# SCHEMATIC_ESP32C3FN4_8thJune2023.net
KiCad netlist of a schematic drawn in Altium Designer
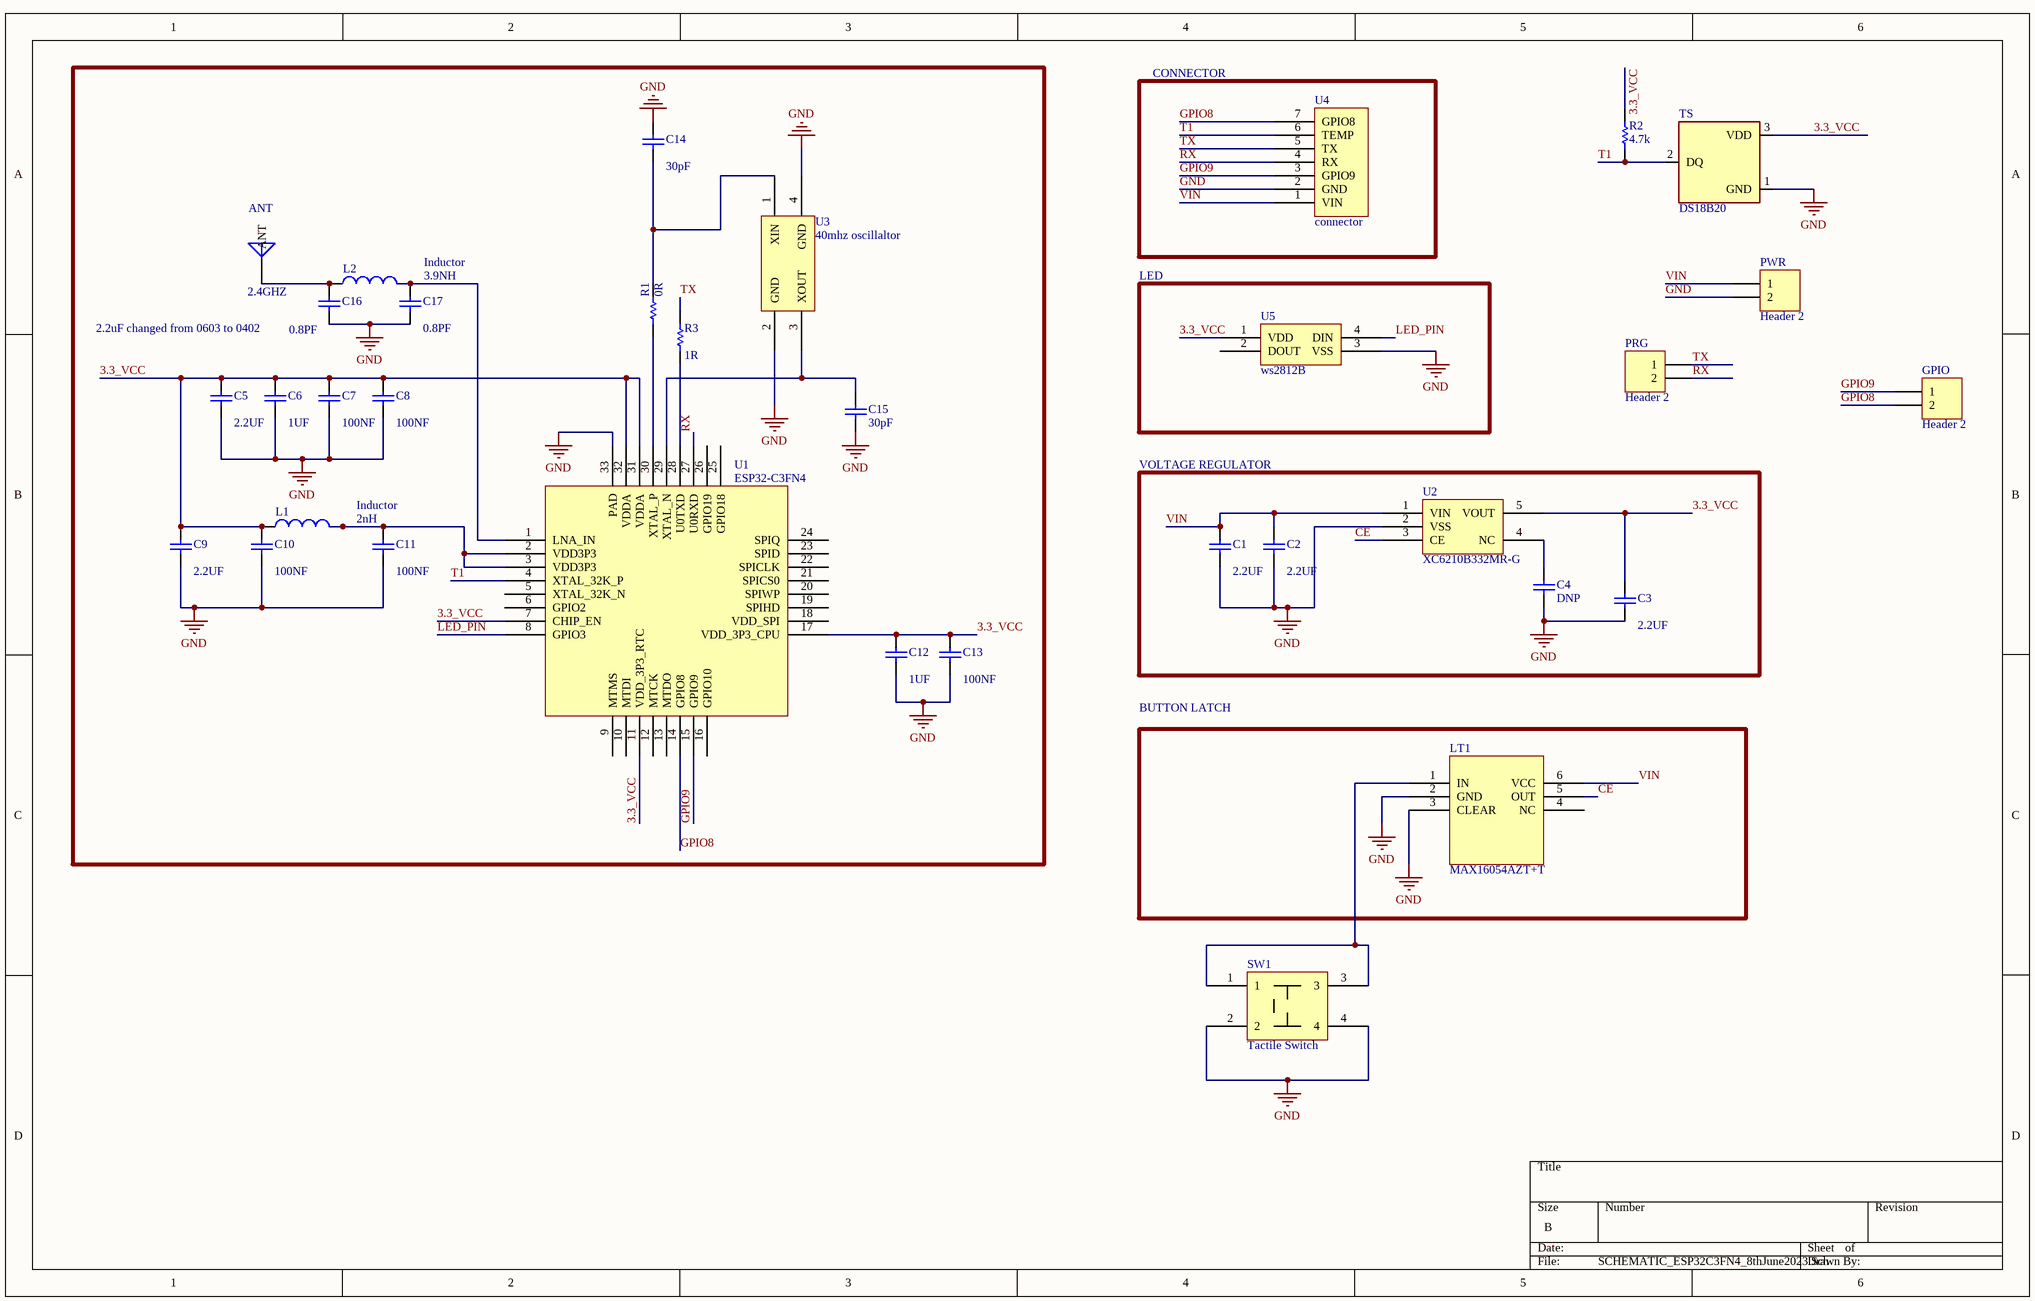
[diagram p0: SCHEMATIC_ESP32C3FN4_8thJune2023.SchDoc]

(export (version "E")
  (design (tool "Eeschema 10.0.6"))
  (components
    (comp (ref "ANT")
      (value "2.4GHZ")
      (footprint "XDCR_2450AT18B100E")
      (description "Generic Antennals")
      (fields (field (name "PUBLISHER") "Altium Limited"))
      (libsource (lib "Miscellaneous Devices") (part "Antenna"))
    )
    (comp (ref "C1")
      (value "2.2UF")
      (footprint "0402-A")
      (description "16V 2.2uF X6S ±10% 0402 Multilayer Ceramic Capacitors MLCC - SMD/SMT ROHS")
      (fields (field (name "Comment") "GRM188C71C225KE11D") (field (name "PUBLISHER") "Altium Limited"))
      (libsource (lib "Miscellaneous Devices") (part "Cap"))
    )
    (comp (ref "C2")
      (value "2.2UF")
      (footprint "0402-A")
      (description "16V 2.2uF X6S ±10% 0402 Multilayer Ceramic Capacitors MLCC - SMD/SMT ROHS")
      (fields (field (name "Comment") "GRM188C71C225KE11D") (field (name "PUBLISHER") "Altium Limited"))
      (libsource (lib "Miscellaneous Devices") (part "Cap"))
    )
    (comp (ref "C3")
      (value "2.2UF")
      (footprint "0402-A")
      (description "16V 2.2uF X6S ±10% 0402 Multilayer Ceramic Capacitors MLCC - SMD/SMT ROHS")
      (fields (field (name "Comment") "GRM188C71C225KE11D") (field (name "PUBLISHER") "Altium Limited"))
      (libsource (lib "Miscellaneous Devices") (part "Cap"))
    )
    (comp (ref "C4")
      (value "DNP")
      (footprint "0402")
      (description "Capacitor")
      (fields (field (name "PUBLISHER") "Altium Limited"))
      (libsource (lib "Miscellaneous Devices") (part "Cap"))
    )
    (comp (ref "C5")
      (value "2.2UF")
      (footprint "0402-A")
      (description "16V 2.2uF X6S ±10% 0402 Multilayer Ceramic Capacitors MLCC - SMD/SMT ROHS")
      (fields (field (name "Comment") "GRM188C71C225KE11D") (field (name "PUBLISHER") "Altium Limited"))
      (libsource (lib "Miscellaneous Devices") (part "Cap"))
    )
    (comp (ref "C6")
      (value "1UF")
      (footprint "0402-A")
      (description "35V 1uF ±10% 0402 Multilayer Ceramic Capacitors MLCC - SMD/SMT ROHS")
      (fields (field (name "Comment") "Cap") (field (name "PUBLISHER") "Altium Limited"))
      (libsource (lib "Miscellaneous Devices") (part "Cap"))
    )
    (comp (ref "C7")
      (value "100NF")
      (footprint "0402-A")
      (description "50V 100nF X7R ±10% 0402 Multilayer Ceramic Capacitors MLCC - SMD/SMT ROHS")
      (fields (field (name "Comment") "Cap") (field (name "PUBLISHER") "Altium Limited"))
      (libsource (lib "Miscellaneous Devices") (part "Cap"))
    )
    (comp (ref "C8")
      (value "100NF")
      (footprint "0402-A")
      (description "50V 100nF X7R ±10% 0402 Multilayer Ceramic Capacitors MLCC - SMD/SMT ROHS")
      (fields (field (name "Comment") "Cap") (field (name "PUBLISHER") "Altium Limited"))
      (libsource (lib "Miscellaneous Devices") (part "Cap"))
    )
    (comp (ref "C9")
      (value "2.2UF")
      (footprint "0402-A")
      (description "16V 2.2uF X6S ±10% 0402 Multilayer Ceramic Capacitors MLCC - SMD/SMT ROHS")
      (fields (field (name "Comment") "GRM188C71C225KE11D") (field (name "PUBLISHER") "Altium Limited"))
      (libsource (lib "Miscellaneous Devices") (part "Cap"))
    )
    (comp (ref "C10")
      (value "100NF")
      (footprint "0402-A")
      (description "50V 100nF X7R ±10% 0402 Multilayer Ceramic Capacitors MLCC - SMD/SMT ROHS")
      (fields (field (name "Comment") "Cap") (field (name "PUBLISHER") "Altium Limited"))
      (libsource (lib "Miscellaneous Devices") (part "Cap"))
    )
    (comp (ref "C11")
      (value "100NF")
      (footprint "0402-A")
      (description "50V 100nF X7R ±10% 0402 Multilayer Ceramic Capacitors MLCC - SMD/SMT ROHS")
      (fields (field (name "Comment") "Cap") (field (name "PUBLISHER") "Altium Limited"))
      (libsource (lib "Miscellaneous Devices") (part "Cap"))
    )
    (comp (ref "C12")
      (value "1UF")
      (footprint "0402-A")
      (description "35V 1uF ±10% 0402 Multilayer Ceramic Capacitors MLCC - SMD/SMT ROHS")
      (fields (field (name "Comment") "Cap") (field (name "PUBLISHER") "Altium Limited"))
      (libsource (lib "Miscellaneous Devices") (part "Cap"))
    )
    (comp (ref "C13")
      (value "100NF")
      (footprint "0402-A")
      (description "50V 100nF X7R ±10% 0402 Multilayer Ceramic Capacitors MLCC - SMD/SMT ROHS")
      (fields (field (name "Comment") "Cap") (field (name "PUBLISHER") "Altium Limited"))
      (libsource (lib "Miscellaneous Devices") (part "Cap"))
    )
    (comp (ref "C14")
      (value "30pF")
      (footprint "1608[0603]")
      (description "Capacitor")
      (fields (field (name "Comment") "Cap") (field (name "PUBLISHER") "Altium Limited"))
      (libsource (lib "Miscellaneous Devices") (part "Cap"))
    )
    (comp (ref "C15")
      (value "30pF")
      (footprint "1608[0603]")
      (description "Capacitor")
      (fields (field (name "Comment") "Cap") (field (name "PUBLISHER") "Altium Limited"))
      (libsource (lib "Miscellaneous Devices") (part "Cap"))
    )
    (comp (ref "C16")
      (value "0.8PF")
      (footprint "0402-A")
      (description "Capacitor")
      (fields (field (name "Comment") "Cap") (field (name "PUBLISHER") "Altium Limited"))
      (libsource (lib "Miscellaneous Devices") (part "Cap"))
    )
    (comp (ref "C17")
      (value "0.8PF")
      (footprint "0402-A")
      (description "Capacitor")
      (fields (field (name "Comment") "Cap") (field (name "PUBLISHER") "Altium Limited"))
      (libsource (lib "Miscellaneous Devices") (part "Cap"))
    )
    (comp (ref "GPIO")
      (value "Header 2")
      (footprint "C1206")
      (description "Header, 2-Pin")
      (fields (field (name "PUBLISHER") "Altium Limited"))
      (libsource (lib "Miscellaneous Connectors") (part "Header 2"))
    )
    (comp (ref "L1")
      (value "Inductor")
      (footprint "1608[0603]")
      (fields (field (name "ALTIUM_VALUE") "2nH") (field (name "PUBLISHER") "Altium Limited"))
      (libsource (lib "Miscellaneous Devices") (part "Inductor"))
    )
    (comp (ref "L2")
      (value "Inductor")
      (footprint "0402-A")
      (fields (field (name "ALTIUM_VALUE") "3.9NH") (field (name "PUBLISHER") "Altium Limited"))
      (libsource (lib "Miscellaneous Devices") (part "Inductor"))
    )
    (comp (ref "LT1")
      (value "MAX16054AZT+T")
      (footprint "SOT95P275X110-6N")
      (libsource (lib "Schlib1") (part "MAX16054AZT+T"))
    )
    (comp (ref "PRG")
      (value "Header 2")
      (footprint "C1206")
      (description "Header, 2-Pin")
      (fields (field (name "PUBLISHER") "Altium Limited"))
      (libsource (lib "") (part "Header 2_1"))
    )
    (comp (ref "PWR")
      (value "Header 2")
      (footprint "C1206")
      (description "Header, 2-Pin")
      (fields (field (name "PUBLISHER") "Altium Limited"))
      (libsource (lib "Miscellaneous Connectors") (part "Header 2"))
    )
    (comp (ref "R1")
      (value "0R")
      (footprint "0402-A")
      (description "62.5mW Thick Film Resistors ±800ppm/℃ ±1% 0Ω 0402 Chip Resistor - Surface Mount ROHS")
      (fields (field (name "Comment") "Res1") (field (name "PUBLISHER") "Altium Limited"))
      (libsource (lib "Miscellaneous Devices") (part "Res1"))
    )
    (comp (ref "R2")
      (value "4.7k")
      (footprint "1608[0603]")
      (description "±5% 4.7kΩ 0603 Chip Resistor - Surface Mount ROHS")
      (fields (field (name "Comment") "SCR0603J4K7") (field (name "PUBLISHER") "Altium Limited"))
      (libsource (lib "Miscellaneous Devices") (part "Res1"))
    )
    (comp (ref "R3")
      (value "1R")
      (footprint "0402-A")
      (description "62.5mW Thick Film Resistors ±1% ±200ppm/℃ 1Ω 0402 Chip Resistor - Surface Mount ROHS")
      (fields (field (name "Comment") "Res1") (field (name "PUBLISHER") "Altium Limited"))
      (libsource (lib "Miscellaneous Devices") (part "Res1"))
    )
    (comp (ref "SW1")
      (value "Tactile Switch")
      (footprint "SKRBACE010")
      (libsource (lib "Schlib1") (part "Tactile Switch"))
    )
    (comp (ref "TS")
      (value "DS18B20")
      (footprint "TO-92-TO92127P495H2044-3")
      (description "Temperature Sensor Digital, Local -55Â°C ~ 125Â°C 12 b TO-92-3")
      (fields (field (name "MF") "Maxim Integrated"))
      (libsource (lib "epsschmtc") (part "DS18B20"))
    )
    (comp (ref "U1")
      (value "ESP32-C3FN4")
      (footprint "QFN50P500X500X90-33N-D")
      (libsource (lib "Schlib1") (part "ESP32-C3F"))
    )
    (comp (ref "U2")
      (value "XC6210B332MR-G")
      (footprint "SOT95P280X130-5N")
      (description "700mA 60dB@(1kHz) Fixed 3.3V~3.3V Positive 6V SOT-25 Linear Voltage Regulators (LDO) ROHS")
      (libsource (lib "Schlib1") (part "XC6210B332MR-G"))
    )
    (comp (ref "U3")
      (value "40mhz oscillaltor")
      (footprint "CRYSTAL-SMD_4P-L3.2-W2.5-BL")
      (description "C3003278")
      (libsource (lib "Schlib1") (part "40mhz oscillaltor"))
    )
    (comp (ref "U4") (value "connector") (libsource (lib "Schlib1") (part "connector")))
    (comp (ref "U5")
      (value "ws2812B")
      (footprint "COM16346")
      (description "RGB SMD5050 Light Emitting Diodes (LED) ROHS")
      (libsource (lib "Schlib1") (part "ws2812B"))
    )
  )
  (nets
    (net (code "1") (name "/3.3_VCC") (class "Default")
      (node (ref "C10") (pin "2") (pinfunction "2_2") (pintype "passive"))
      (node (ref "C12") (pin "2") (pinfunction "2_2") (pintype "passive"))
      (node (ref "C13") (pin "2") (pinfunction "2_2") (pintype "passive"))
      (node (ref "C3") (pin "2") (pinfunction "2_2") (pintype "passive"))
      (node (ref "C5") (pin "2") (pinfunction "2_2") (pintype "passive"))
      (node (ref "C6") (pin "2") (pinfunction "2_2") (pintype "passive"))
      (node (ref "C7") (pin "2") (pinfunction "2_2") (pintype "passive"))
      (node (ref "C8") (pin "2") (pinfunction "2_2") (pintype "passive"))
      (node (ref "C9") (pin "2") (pinfunction "2_2") (pintype "passive"))
      (node (ref "L1") (pin "1") (pinfunction "1_1") (pintype "passive"))
      (node (ref "R2") (pin "1") (pinfunction "1_1") (pintype "passive"))
      (node (ref "TS") (pin "3") (pinfunction "VDD_3") (pintype "power_in"))
      (node (ref "U1") (pin "11") (pinfunction "VDD_3P3_RTC_11") (pintype "passive"))
      (node (ref "U1") (pin "17") (pinfunction "VDD_3P3_CPU_17") (pintype "passive"))
      (node (ref "U1") (pin "31") (pinfunction "VDDA_31") (pintype "passive"))
      (node (ref "U1") (pin "32") (pinfunction "VDDA_32") (pintype "passive"))
      (node (ref "U1") (pin "7") (pinfunction "CHIP_EN_7") (pintype "passive"))
      (node (ref "U2") (pin "5") (pinfunction "VOUT_5") (pintype "passive"))
      (node (ref "U5") (pin "1") (pinfunction "VDD_1") (pintype "passive"))
    )
    (net (code "2") (name "/CE") (class "Default")
      (node (ref "LT1") (pin "5") (pinfunction "OUT_5") (pintype "passive"))
      (node (ref "U2") (pin "3") (pinfunction "CE_3") (pintype "passive"))
    )
    (net (code "3") (name "/GPIO8") (class "Default")
      (node (ref "GPIO") (pin "2") (pinfunction "2_2") (pintype "passive"))
      (node (ref "U1") (pin "14") (pinfunction "GPIO8_14") (pintype "passive"))
      (node (ref "U4") (pin "7") (pinfunction "GPIO8_7") (pintype "passive"))
    )
    (net (code "4") (name "/GPIO9") (class "Default")
      (node (ref "GPIO") (pin "1") (pinfunction "1_1") (pintype "passive"))
      (node (ref "U1") (pin "15") (pinfunction "GPIO9_15") (pintype "passive"))
      (node (ref "U4") (pin "3") (pinfunction "GPIO9_3") (pintype "passive"))
    )
    (net (code "5") (name "/LED_PIN") (class "Default")
      (node (ref "U1") (pin "8") (pinfunction "GPIO3_8") (pintype "passive"))
      (node (ref "U5") (pin "4") (pinfunction "DIN_4") (pintype "passive"))
    )
    (net (code "6") (name "/RX") (class "Default")
      (node (ref "PRG") (pin "2") (pinfunction "2_2") (pintype "passive"))
      (node (ref "U1") (pin "27") (pinfunction "U0RXD_27") (pintype "passive"))
      (node (ref "U4") (pin "4") (pinfunction "RX_4") (pintype "passive"))
    )
    (net (code "7") (name "/T1") (class "Default")
      (node (ref "R2") (pin "2") (pinfunction "2_2") (pintype "passive"))
      (node (ref "TS") (pin "2") (pinfunction "DQ_2") (pintype "passive"))
      (node (ref "U1") (pin "4") (pinfunction "XTAL_32K_P_4") (pintype "passive"))
      (node (ref "U4") (pin "6") (pinfunction "TEMP_6") (pintype "passive"))
    )
    (net (code "8") (name "/TX") (class "Default")
      (node (ref "PRG") (pin "1") (pinfunction "1_1") (pintype "passive"))
      (node (ref "R3") (pin "1") (pinfunction "1_1") (pintype "passive"))
      (node (ref "U4") (pin "5") (pinfunction "TX_5") (pintype "passive"))
    )
    (net (code "9") (name "/VIN") (class "Default")
      (node (ref "C1") (pin "2") (pinfunction "2_2") (pintype "passive"))
      (node (ref "C2") (pin "2") (pinfunction "2_2") (pintype "passive"))
      (node (ref "LT1") (pin "6") (pinfunction "VCC_6") (pintype "passive"))
      (node (ref "PWR") (pin "1") (pinfunction "1_1") (pintype "passive"))
      (node (ref "U2") (pin "1") (pinfunction "VIN_1") (pintype "passive"))
      (node (ref "U4") (pin "1") (pinfunction "VIN_1") (pintype "passive"))
    )
    (net (code "10") (name "GND") (class "Default")
      (node (ref "C1") (pin "1") (pinfunction "1_1") (pintype "passive"))
      (node (ref "C10") (pin "1") (pinfunction "1_1") (pintype "passive"))
      (node (ref "C11") (pin "1") (pinfunction "1_1") (pintype "passive"))
      (node (ref "C12") (pin "1") (pinfunction "1_1") (pintype "passive"))
      (node (ref "C13") (pin "1") (pinfunction "1_1") (pintype "passive"))
      (node (ref "C14") (pin "2") (pinfunction "2_2") (pintype "passive"))
      (node (ref "C15") (pin "2") (pinfunction "2_2") (pintype "passive"))
      (node (ref "C16") (pin "1") (pinfunction "1_1") (pintype "passive"))
      (node (ref "C17") (pin "1") (pinfunction "1_1") (pintype "passive"))
      (node (ref "C2") (pin "1") (pinfunction "1_1") (pintype "passive"))
      (node (ref "C3") (pin "1") (pinfunction "1_1") (pintype "passive"))
      (node (ref "C4") (pin "1") (pinfunction "1_1") (pintype "passive"))
      (node (ref "C5") (pin "1") (pinfunction "1_1") (pintype "passive"))
      (node (ref "C6") (pin "1") (pinfunction "1_1") (pintype "passive"))
      (node (ref "C7") (pin "1") (pinfunction "1_1") (pintype "passive"))
      (node (ref "C8") (pin "1") (pinfunction "1_1") (pintype "passive"))
      (node (ref "C9") (pin "1") (pinfunction "1_1") (pintype "passive"))
      (node (ref "LT1") (pin "2") (pinfunction "GND_2") (pintype "passive"))
      (node (ref "LT1") (pin "3") (pinfunction "CLEAR_3") (pintype "passive"))
      (node (ref "PWR") (pin "2") (pinfunction "2_2") (pintype "passive"))
      (node (ref "SW1") (pin "2") (pinfunction "2_2") (pintype "passive"))
      (node (ref "SW1") (pin "4") (pinfunction "4_4") (pintype "passive"))
      (node (ref "TS") (pin "1") (pinfunction "GND_1") (pintype "power_in"))
      (node (ref "U1") (pin "33") (pinfunction "PAD_33") (pintype "passive"))
      (node (ref "U2") (pin "2") (pinfunction "VSS_2") (pintype "passive"))
      (node (ref "U3") (pin "2") (pinfunction "GND_2") (pintype "passive"))
      (node (ref "U3") (pin "4") (pinfunction "GND_4") (pintype "passive"))
      (node (ref "U4") (pin "2") (pinfunction "GND_2") (pintype "passive"))
      (node (ref "U5") (pin "3") (pinfunction "VSS_3") (pintype "passive"))
    )
    (net (code "11") (name "Net-(ANT-ANT)") (class "Default")
      (node (ref "ANT") (pin "1") (pinfunction "ANT_1") (pintype "passive"))
      (node (ref "C16") (pin "2") (pinfunction "2_2") (pintype "passive"))
      (node (ref "L2") (pin "1") (pinfunction "1_1") (pintype "passive"))
    )
    (net (code "12") (name "Net-(C11-Pad2)") (class "Default")
      (node (ref "C11") (pin "2") (pinfunction "2_2") (pintype "passive"))
      (node (ref "L1") (pin "2") (pinfunction "2_2") (pintype "passive"))
      (node (ref "U1") (pin "2") (pinfunction "VDD3P3_2") (pintype "passive"))
      (node (ref "U1") (pin "3") (pinfunction "VDD3P3_3") (pintype "passive"))
    )
    (net (code "13") (name "Net-(LT1-IN)") (class "Default")
      (node (ref "LT1") (pin "1") (pinfunction "IN_1") (pintype "passive"))
      (node (ref "SW1") (pin "1") (pinfunction "1_1") (pintype "passive"))
      (node (ref "SW1") (pin "3") (pinfunction "3_3") (pintype "passive"))
    )
    (net (code "14") (name "Net-(U1-LNA_IN)") (class "Default")
      (node (ref "C17") (pin "2") (pinfunction "2_2") (pintype "passive"))
      (node (ref "L2") (pin "2") (pinfunction "2_2") (pintype "passive"))
      (node (ref "U1") (pin "1") (pinfunction "LNA_IN_1") (pintype "passive"))
    )
    (net (code "15") (name "Net-(U1-U0TXD)") (class "Default")
      (node (ref "R3") (pin "2") (pinfunction "2_2") (pintype "passive"))
      (node (ref "U1") (pin "28") (pinfunction "U0TXD_28") (pintype "passive"))
    )
    (net (code "16") (name "Net-(U1-XTAL_N)") (class "Default")
      (node (ref "C15") (pin "1") (pinfunction "1_1") (pintype "passive"))
      (node (ref "U1") (pin "29") (pinfunction "XTAL_N_29") (pintype "passive"))
      (node (ref "U3") (pin "3") (pinfunction "XOUT_3") (pintype "passive"))
    )
    (net (code "17") (name "Net-(U1-XTAL_P)") (class "Default")
      (node (ref "R1") (pin "2") (pinfunction "2_2") (pintype "passive"))
      (node (ref "U1") (pin "30") (pinfunction "XTAL_P_30") (pintype "passive"))
    )
    (net (code "18") (name "Net-(U2-NC)") (class "Default")
      (node (ref "C4") (pin "2") (pinfunction "2_2") (pintype "passive"))
      (node (ref "U2") (pin "4") (pinfunction "NC_4") (pintype "passive"))
    )
    (net (code "19") (name "Net-(U3-XIN)") (class "Default")
      (node (ref "C14") (pin "1") (pinfunction "1_1") (pintype "passive"))
      (node (ref "R1") (pin "1") (pinfunction "1_1") (pintype "passive"))
      (node (ref "U3") (pin "1") (pinfunction "XIN_1") (pintype "passive"))
    )
    (net (code "20") (name "unconnected-(LT1-NC-Pad4)") (class "Default")
      (node (ref "LT1") (pin "4") (pinfunction "NC_4") (pintype "passive"))
    )
    (net (code "21") (name "unconnected-(U1-GPIO2-Pad6)") (class "Default")
      (node (ref "U1") (pin "6") (pinfunction "GPIO2_6") (pintype "passive"))
    )
    (net (code "22") (name "unconnected-(U1-GPIO10-Pad16)") (class "Default")
      (node (ref "U1") (pin "16") (pinfunction "GPIO10_16") (pintype "passive"))
    )
    (net (code "23") (name "unconnected-(U1-GPIO18-Pad25)") (class "Default")
      (node (ref "U1") (pin "25") (pinfunction "GPIO18_25") (pintype "passive"))
    )
    (net (code "24") (name "unconnected-(U1-GPIO19-Pad26)") (class "Default")
      (node (ref "U1") (pin "26") (pinfunction "GPIO19_26") (pintype "passive"))
    )
    (net (code "25") (name "unconnected-(U1-MTCK-Pad12)") (class "Default")
      (node (ref "U1") (pin "12") (pinfunction "MTCK_12") (pintype "passive"))
    )
    (net (code "26") (name "unconnected-(U1-MTDI-Pad10)") (class "Default")
      (node (ref "U1") (pin "10") (pinfunction "MTDI_10") (pintype "passive"))
    )
    (net (code "27") (name "unconnected-(U1-MTDO-Pad13)") (class "Default")
      (node (ref "U1") (pin "13") (pinfunction "MTDO_13") (pintype "passive"))
    )
    (net (code "28") (name "unconnected-(U1-MTMS-Pad9)") (class "Default")
      (node (ref "U1") (pin "9") (pinfunction "MTMS_9") (pintype "passive"))
    )
    (net (code "29") (name "unconnected-(U1-SPICLK-Pad22)") (class "Default")
      (node (ref "U1") (pin "22") (pinfunction "SPICLK_22") (pintype "passive"))
    )
    (net (code "30") (name "unconnected-(U1-SPICS0-Pad21)") (class "Default")
      (node (ref "U1") (pin "21") (pinfunction "SPICS0_21") (pintype "passive"))
    )
    (net (code "31") (name "unconnected-(U1-SPID-Pad23)") (class "Default")
      (node (ref "U1") (pin "23") (pinfunction "SPID_23") (pintype "passive"))
    )
    (net (code "32") (name "unconnected-(U1-SPIHD-Pad19)") (class "Default")
      (node (ref "U1") (pin "19") (pinfunction "SPIHD_19") (pintype "passive"))
    )
    (net (code "33") (name "unconnected-(U1-SPIQ-Pad24)") (class "Default")
      (node (ref "U1") (pin "24") (pinfunction "SPIQ_24") (pintype "passive"))
    )
    (net (code "34") (name "unconnected-(U1-SPIWP-Pad20)") (class "Default")
      (node (ref "U1") (pin "20") (pinfunction "SPIWP_20") (pintype "passive"))
    )
    (net (code "35") (name "unconnected-(U1-VDD_SPI-Pad18)") (class "Default")
      (node (ref "U1") (pin "18") (pinfunction "VDD_SPI_18") (pintype "passive"))
    )
    (net (code "36") (name "unconnected-(U1-XTAL_32K_N-Pad5)") (class "Default")
      (node (ref "U1") (pin "5") (pinfunction "XTAL_32K_N_5") (pintype "passive"))
    )
    (net (code "37") (name "unconnected-(U5-DOUT-Pad2)") (class "Default")
      (node (ref "U5") (pin "2") (pinfunction "DOUT_2") (pintype "passive"))
    )
  )
)
